# steering_servo.net
KiCad netlist of a schematic drawn in Altium Designer
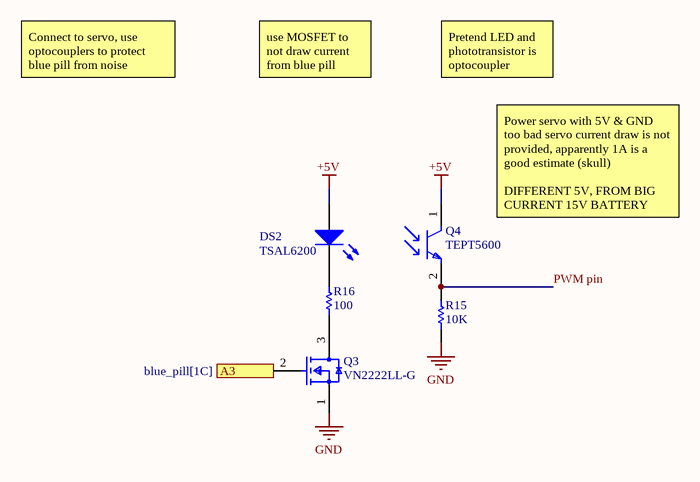
[diagram p0: steering_servo.SchDoc]

(export (version "E")
  (design (tool "Eeschema 10.0.6"))
  (components
    (comp (ref "DS2")
      (value "TSAL6200")
      (footprint "VISH-TSAL6200")
      (fields (field (name "MANUFACTURER") "Vishay"))
      (libsource (lib "Altium Content Vault") (part "LED-AK-2"))
    )
    (comp (ref "Q3")
      (value "VN2222LL-G")
      (footprint "FP-VN2222LL-G-MFG")
      (description "MOSFET N-CH 60V 0.23A TO92-3")
      (libsource (lib "Altium Content Vault") (part "4ab27c3d3892bfd5e8942bbbfba2a96"))
    )
    (comp (ref "Q4")
      (value "TEPT5600")
      (footprint "FP-6_544-5185_03-4-MFG")
      (description "SENSOR PHOTO 570NM TOP VIEW RAD")
      (libsource (lib "Altium Content Vault") (part "9456f77f46cf90b3cfae45295d5ca59"))
    )
    (comp (ref "R15")
      (value "10K")
      (description "Resistor")
      (libsource (lib "Simulation Generic Components") (part "Resistor"))
    )
    (comp (ref "R16")
      (value "100")
      (description "Resistor")
      (libsource (lib "Simulation Generic Components") (part "Resistor"))
    )
  )
  (nets
    (net (code "1") (name "+5V") (class "Default")
      (node (ref "DS2") (pin "1") (pinfunction "A_1") (pintype "passive"))
      (node (ref "Q4") (pin "1") (pinfunction "C_1") (pintype "passive"))
    )
    (net (code "2") (name "/A3") (class "Default")
      (node (ref "Q3") (pin "2") (pinfunction "GATE_2") (pintype "passive"))
    )
    (net (code "3") (name "/PWM pin") (class "Default")
      (node (ref "Q4") (pin "2") (pinfunction "E_2") (pintype "passive"))
      (node (ref "R15") (pin "1") (pinfunction "1_1") (pintype "passive"))
    )
    (net (code "4") (name "GND") (class "Default")
      (node (ref "Q3") (pin "1") (pinfunction "SOURCE_1") (pintype "passive"))
      (node (ref "R15") (pin "2") (pinfunction "2_2") (pintype "passive"))
    )
    (net (code "5") (name "Net-(DS2-K)") (class "Default")
      (node (ref "DS2") (pin "2") (pinfunction "K_2") (pintype "passive"))
      (node (ref "R16") (pin "1") (pinfunction "1_1") (pintype "passive"))
    )
    (net (code "6") (name "Net-(Q3-DRAIN)") (class "Default")
      (node (ref "Q3") (pin "3") (pinfunction "DRAIN_3") (pintype "passive"))
      (node (ref "R16") (pin "2") (pinfunction "2_2") (pintype "passive"))
    )
  )
)
